# slider4.net
KiCad netlist of a schematic drawn in EAGLE
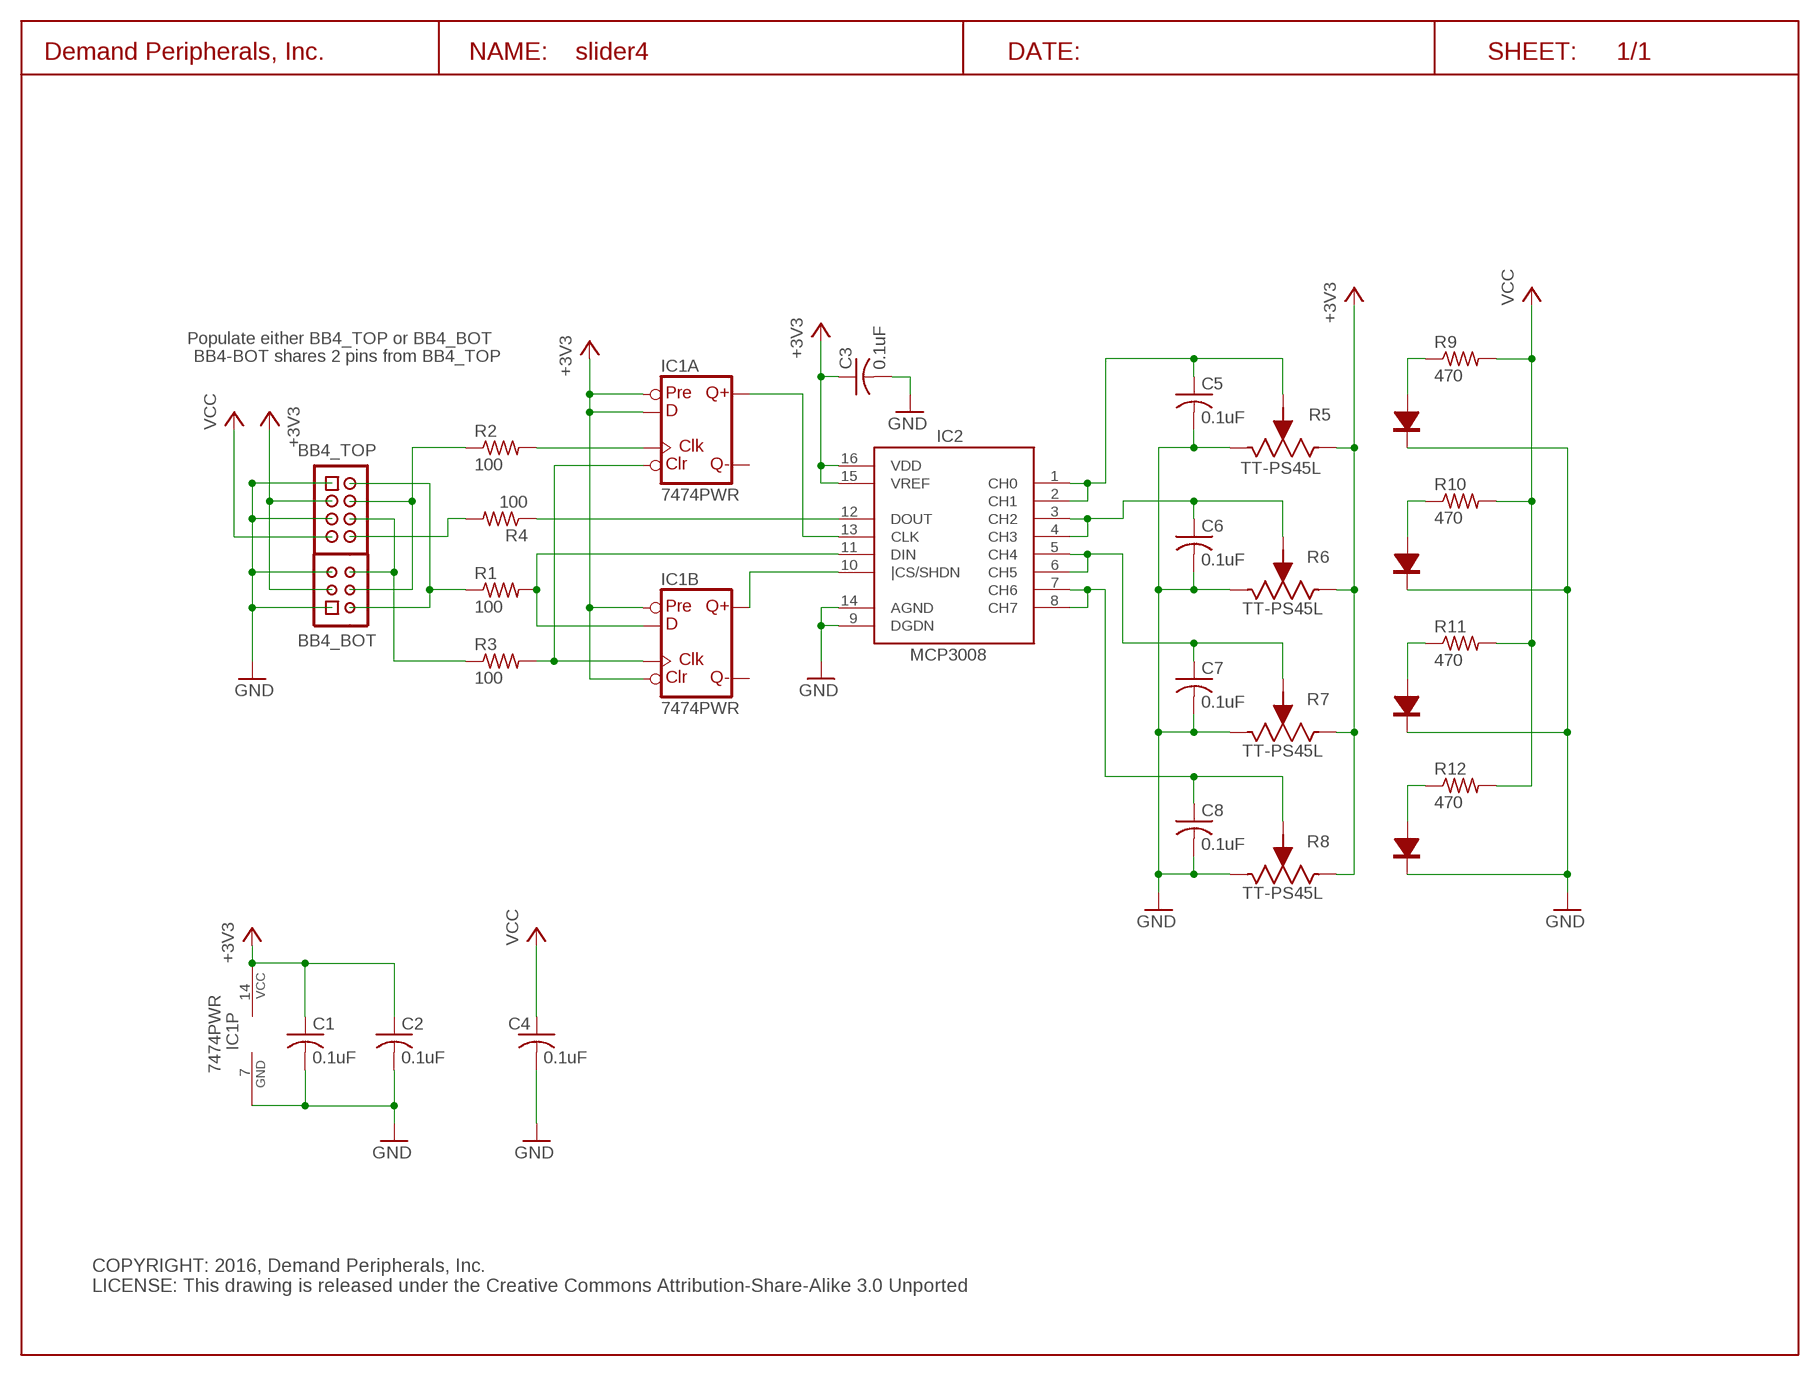
[diagram p0: schematic, sheet 1]

(export (version "E")
  (design (tool "Eeschema 10.0.6"))
  (components
    (comp (ref "BB4_BOT")
      (value "Hdr3x2")
      (footprint "eagle-import:HDR-3X2")
      (libsource (lib "eagle-import") (part "HDR-3X2"))
    )
    (comp (ref "BB4_TOP")
      (value "Hdr4x2")
      (footprint "eagle-import:HDR-4X2")
      (libsource (lib "eagle-import") (part "HDR-4X2-SHR"))
    )
    (comp (ref "C1")
      (value "0.1uF")
      (footprint "eagle-import:C0603")
      (libsource (lib "eagle-import") (part "C0.1UF_C0603"))
    )
    (comp (ref "C2")
      (value "0.1uF")
      (footprint "eagle-import:C0603")
      (libsource (lib "eagle-import") (part "C0.1UF_C0603"))
    )
    (comp (ref "C3")
      (value "0.1uF")
      (footprint "eagle-import:C0603")
      (libsource (lib "eagle-import") (part "C0.1UF_C0603"))
    )
    (comp (ref "C4")
      (value "0.1uF")
      (footprint "eagle-import:C0603")
      (libsource (lib "eagle-import") (part "C0.1UF_C0603"))
    )
    (comp (ref "C5")
      (value "0.1uF")
      (footprint "eagle-import:C0603")
      (libsource (lib "eagle-import") (part "C0.1UF_C0603"))
    )
    (comp (ref "C6")
      (value "0.1uF")
      (footprint "eagle-import:C0603")
      (libsource (lib "eagle-import") (part "C0.1UF_C0603"))
    )
    (comp (ref "C7")
      (value "0.1uF")
      (footprint "eagle-import:C0603")
      (libsource (lib "eagle-import") (part "C0.1UF_C0603"))
    )
    (comp (ref "C8")
      (value "0.1uF")
      (footprint "eagle-import:C0603")
      (libsource (lib "eagle-import") (part "C0.1UF_C0603"))
    )
    (comp (ref "IC1")
      (value "7474PWR")
      (footprint "eagle-import:SO14")
      (libsource (lib "eagle-import") (part "74AHC74"))
    )
    (comp (ref "IC2")
      (value "MCP3008")
      (footprint "eagle-import:SO16")
      (libsource (lib "eagle-import") (part "MCP3008"))
    )
    (comp (ref "R1")
      (value "100")
      (footprint "eagle-import:R0603")
      (libsource (lib "eagle-import") (part "R100_R0603"))
    )
    (comp (ref "R2")
      (value "100")
      (footprint "eagle-import:R0603")
      (libsource (lib "eagle-import") (part "R100_R0603"))
    )
    (comp (ref "R3")
      (value "100")
      (footprint "eagle-import:R0603")
      (libsource (lib "eagle-import") (part "R100_R0603"))
    )
    (comp (ref "R4")
      (value "100")
      (footprint "eagle-import:R0603")
      (libsource (lib "eagle-import") (part "R100_R0603"))
    )
    (comp (ref "R5")
      (value "TT-PS45L")
      (footprint "eagle-import:TT-PS45L")
      (libsource (lib "eagle-import") (part "TT-PS45L"))
    )
    (comp (ref "R6")
      (value "TT-PS45L")
      (footprint "eagle-import:TT-PS45L")
      (libsource (lib "eagle-import") (part "TT-PS45L"))
    )
    (comp (ref "R7")
      (value "TT-PS45L")
      (footprint "eagle-import:TT-PS45L")
      (libsource (lib "eagle-import") (part "TT-PS45L"))
    )
    (comp (ref "R8")
      (value "TT-PS45L")
      (footprint "eagle-import:TT-PS45L")
      (libsource (lib "eagle-import") (part "TT-PS45L"))
    )
    (comp (ref "R9")
      (value "470")
      (footprint "eagle-import:R0603")
      (libsource (lib "eagle-import") (part "R470_R0603"))
    )
    (comp (ref "R10")
      (value "470")
      (footprint "eagle-import:R0603")
      (libsource (lib "eagle-import") (part "R470_R0603"))
    )
    (comp (ref "R11")
      (value "470")
      (footprint "eagle-import:R0603")
      (libsource (lib "eagle-import") (part "R470_R0603"))
    )
    (comp (ref "R12")
      (value "470")
      (footprint "eagle-import:R0603")
      (libsource (lib "eagle-import") (part "R470_R0603"))
    )
    (comp (ref "U$7")
      (value "DP_FRAME_L")
      (footprint "eagle-import:LETTER_L")
      (libsource (lib "eagle-import") (part "DP_FRAME_L"))
    )
  )
  (nets
    (net (code "1") (name "+3V3") (class "Default")
      (node (ref "BB4_BOT") (pin "3") (pinfunction "3_3") (pintype "passive"))
      (node (ref "BB4_TOP") (pin "3") (pinfunction "3_3") (pintype "passive"))
      (node (ref "C1") (pin "1") (pinfunction "1_1") (pintype "passive"))
      (node (ref "C2") (pin "1") (pinfunction "1_1") (pintype "passive"))
      (node (ref "C3") (pin "1") (pinfunction "1_1") (pintype "passive"))
      (node (ref "IC1") (pin "10") (pinfunction "PRE_10") (pintype "input"))
      (node (ref "IC1") (pin "13") (pinfunction "CLR_13") (pintype "input"))
      (node (ref "IC1") (pin "14") (pinfunction "VCC_14") (pintype "power_in"))
      (node (ref "IC1") (pin "2") (pinfunction "D_2") (pintype "input"))
      (node (ref "IC1") (pin "4") (pinfunction "PRE_4") (pintype "input"))
      (node (ref "IC2") (pin "15") (pinfunction "VREF_15") (pintype "bidirectional"))
      (node (ref "IC2") (pin "16") (pinfunction "VDD_16") (pintype "bidirectional"))
      (node (ref "R5") (pin "P$2") (pinfunction "2_P$2") (pintype "passive"))
      (node (ref "R6") (pin "P$2") (pinfunction "2_P$2") (pintype "passive"))
      (node (ref "R7") (pin "P$2") (pinfunction "2_P$2") (pintype "passive"))
      (node (ref "R8") (pin "P$2") (pinfunction "2_P$2") (pintype "passive"))
    )
    (net (code "2") (name "GND") (class "Default")
      (node (ref "BB4_BOT") (pin "1") (pinfunction "1_1") (pintype "passive"))
      (node (ref "BB4_BOT") (pin "5") (pinfunction "5_5") (pintype "passive"))
      (node (ref "BB4_TOP") (pin "1") (pinfunction "1_1") (pintype "passive"))
      (node (ref "BB4_TOP") (pin "5") (pinfunction "5_5") (pintype "passive"))
      (node (ref "C1") (pin "2") (pinfunction "2_2") (pintype "passive"))
      (node (ref "C2") (pin "2") (pinfunction "2_2") (pintype "passive"))
      (node (ref "C3") (pin "2") (pinfunction "2_2") (pintype "passive"))
      (node (ref "C4") (pin "2") (pinfunction "2_2") (pintype "passive"))
      (node (ref "C5") (pin "2") (pinfunction "2_2") (pintype "passive"))
      (node (ref "C6") (pin "2") (pinfunction "2_2") (pintype "passive"))
      (node (ref "C7") (pin "2") (pinfunction "2_2") (pintype "passive"))
      (node (ref "C8") (pin "2") (pinfunction "2_2") (pintype "passive"))
      (node (ref "IC1") (pin "7") (pinfunction "GND_7") (pintype "power_in"))
      (node (ref "IC2") (pin "14") (pinfunction "AGND_14") (pintype "bidirectional"))
      (node (ref "IC2") (pin "9") (pinfunction "DGDN_9") (pintype "bidirectional"))
      (node (ref "R5") (pin "P$4") (pinfunction "5_P$4") (pintype "passive"))
      (node (ref "R5") (pin "P$6") (pinfunction "6_P$6") (pintype "passive"))
      (node (ref "R6") (pin "P$4") (pinfunction "5_P$4") (pintype "passive"))
      (node (ref "R6") (pin "P$6") (pinfunction "6_P$6") (pintype "passive"))
      (node (ref "R7") (pin "P$4") (pinfunction "5_P$4") (pintype "passive"))
      (node (ref "R7") (pin "P$6") (pinfunction "6_P$6") (pintype "passive"))
      (node (ref "R8") (pin "P$4") (pinfunction "5_P$4") (pintype "passive"))
      (node (ref "R8") (pin "P$6") (pinfunction "6_P$6") (pintype "passive"))
    )
    (net (code "3") (name "Net-(BB4_BOT-Pad2)") (class "Default")
      (node (ref "BB4_BOT") (pin "2") (pinfunction "2_2") (pintype "passive"))
      (node (ref "BB4_TOP") (pin "2") (pinfunction "2_2") (pintype "passive"))
      (node (ref "R1") (pin "1") (pinfunction "1_1") (pintype "passive"))
    )
    (net (code "4") (name "Net-(BB4_BOT-Pad4)") (class "Default")
      (node (ref "BB4_BOT") (pin "4") (pinfunction "4_4") (pintype "passive"))
      (node (ref "BB4_TOP") (pin "4") (pinfunction "4_4") (pintype "passive"))
      (node (ref "R2") (pin "1") (pinfunction "1_1") (pintype "passive"))
    )
    (net (code "5") (name "Net-(BB4_BOT-Pad6)") (class "Default")
      (node (ref "BB4_BOT") (pin "6") (pinfunction "6_6") (pintype "passive"))
      (node (ref "BB4_TOP") (pin "6") (pinfunction "6_6") (pintype "passive"))
      (node (ref "R3") (pin "1") (pinfunction "1_1") (pintype "passive"))
    )
    (net (code "6") (name "Net-(BB4_TOP-Pad8)") (class "Default")
      (node (ref "BB4_TOP") (pin "8") (pinfunction "8_8") (pintype "passive"))
      (node (ref "R4") (pin "2") (pinfunction "2_2") (pintype "passive"))
    )
    (net (code "7") (name "Net-(IC1A-CLK)") (class "Default")
      (node (ref "IC1") (pin "3") (pinfunction "CLK_3") (pintype "input"))
      (node (ref "R2") (pin "2") (pinfunction "2_2") (pintype "passive"))
    )
    (net (code "8") (name "Net-(IC1A-CLR)") (class "Default")
      (node (ref "IC1") (pin "1") (pinfunction "CLR_1") (pintype "input"))
      (node (ref "IC1") (pin "11") (pinfunction "CLK_11") (pintype "input"))
      (node (ref "R3") (pin "2") (pinfunction "2_2") (pintype "passive"))
    )
    (net (code "9") (name "Net-(IC1A-Q)") (class "Default")
      (node (ref "IC1") (pin "5") (pinfunction "Q_5") (pintype "output"))
      (node (ref "IC2") (pin "13") (pinfunction "CLK_13") (pintype "bidirectional"))
    )
    (net (code "10") (name "Net-(IC1B-D)") (class "Default")
      (node (ref "IC1") (pin "12") (pinfunction "D_12") (pintype "input"))
      (node (ref "IC2") (pin "11") (pinfunction "DIN_11") (pintype "bidirectional"))
      (node (ref "R1") (pin "2") (pinfunction "2_2") (pintype "passive"))
    )
    (net (code "11") (name "Net-(IC1B-Q)") (class "Default")
      (node (ref "IC1") (pin "9") (pinfunction "Q_9") (pintype "output"))
      (node (ref "IC2") (pin "10") (pinfunction "|CS/SHDN_10") (pintype "bidirectional"))
    )
    (net (code "12") (name "Net-(IC2-CH0)") (class "Default")
      (node (ref "C5") (pin "1") (pinfunction "1_1") (pintype "passive"))
      (node (ref "IC2") (pin "1") (pinfunction "CH0_1") (pintype "bidirectional"))
      (node (ref "IC2") (pin "2") (pinfunction "CH1_2") (pintype "bidirectional"))
      (node (ref "R5") (pin "P$1") (pinfunction "1_P$1") (pintype "passive"))
    )
    (net (code "13") (name "Net-(IC2-CH2)") (class "Default")
      (node (ref "C6") (pin "1") (pinfunction "1_1") (pintype "passive"))
      (node (ref "IC2") (pin "3") (pinfunction "CH2_3") (pintype "bidirectional"))
      (node (ref "IC2") (pin "4") (pinfunction "CH3_4") (pintype "bidirectional"))
      (node (ref "R6") (pin "P$1") (pinfunction "1_P$1") (pintype "passive"))
    )
    (net (code "14") (name "Net-(IC2-CH4)") (class "Default")
      (node (ref "C7") (pin "1") (pinfunction "1_1") (pintype "passive"))
      (node (ref "IC2") (pin "5") (pinfunction "CH4_5") (pintype "bidirectional"))
      (node (ref "IC2") (pin "6") (pinfunction "CH5_6") (pintype "bidirectional"))
      (node (ref "R7") (pin "P$1") (pinfunction "1_P$1") (pintype "passive"))
    )
    (net (code "15") (name "Net-(IC2-CH6)") (class "Default")
      (node (ref "C8") (pin "1") (pinfunction "1_1") (pintype "passive"))
      (node (ref "IC2") (pin "7") (pinfunction "CH6_7") (pintype "bidirectional"))
      (node (ref "IC2") (pin "8") (pinfunction "CH7_8") (pintype "bidirectional"))
      (node (ref "R8") (pin "P$1") (pinfunction "1_P$1") (pintype "passive"))
    )
    (net (code "16") (name "Net-(IC2-DOUT)") (class "Default")
      (node (ref "IC2") (pin "12") (pinfunction "DOUT_12") (pintype "bidirectional"))
      (node (ref "R4") (pin "1") (pinfunction "1_1") (pintype "passive"))
    )
    (net (code "17") (name "Net-(R5-4)") (class "Default")
      (node (ref "R5") (pin "P$5") (pinfunction "4_P$5") (pintype "passive"))
      (node (ref "R9") (pin "1") (pinfunction "1_1") (pintype "passive"))
    )
    (net (code "18") (name "Net-(R6-4)") (class "Default")
      (node (ref "R10") (pin "1") (pinfunction "1_1") (pintype "passive"))
      (node (ref "R6") (pin "P$5") (pinfunction "4_P$5") (pintype "passive"))
    )
    (net (code "19") (name "Net-(R7-4)") (class "Default")
      (node (ref "R11") (pin "1") (pinfunction "1_1") (pintype "passive"))
      (node (ref "R7") (pin "P$5") (pinfunction "4_P$5") (pintype "passive"))
    )
    (net (code "20") (name "Net-(R8-4)") (class "Default")
      (node (ref "R12") (pin "1") (pinfunction "1_1") (pintype "passive"))
      (node (ref "R8") (pin "P$5") (pinfunction "4_P$5") (pintype "passive"))
    )
    (net (code "21") (name "VCC") (class "Default")
      (node (ref "BB4_TOP") (pin "7") (pinfunction "7_7") (pintype "passive"))
      (node (ref "C4") (pin "1") (pinfunction "1_1") (pintype "passive"))
      (node (ref "R10") (pin "2") (pinfunction "2_2") (pintype "passive"))
      (node (ref "R11") (pin "2") (pinfunction "2_2") (pintype "passive"))
      (node (ref "R12") (pin "2") (pinfunction "2_2") (pintype "passive"))
      (node (ref "R9") (pin "2") (pinfunction "2_2") (pintype "passive"))
    )
    (net (code "22") (name "unconnected-(IC1A-~{Q}-Pad6)") (class "Default")
      (node (ref "IC1") (pin "6") (pinfunction "~{Q}_6") (pintype "output"))
    )
    (net (code "23") (name "unconnected-(IC1B-~{Q}-Pad8)") (class "Default")
      (node (ref "IC1") (pin "8") (pinfunction "~{Q}_8") (pintype "output"))
    )
  )
)
